# beod.net
KiCad netlist of a schematic drawn in EAGLE
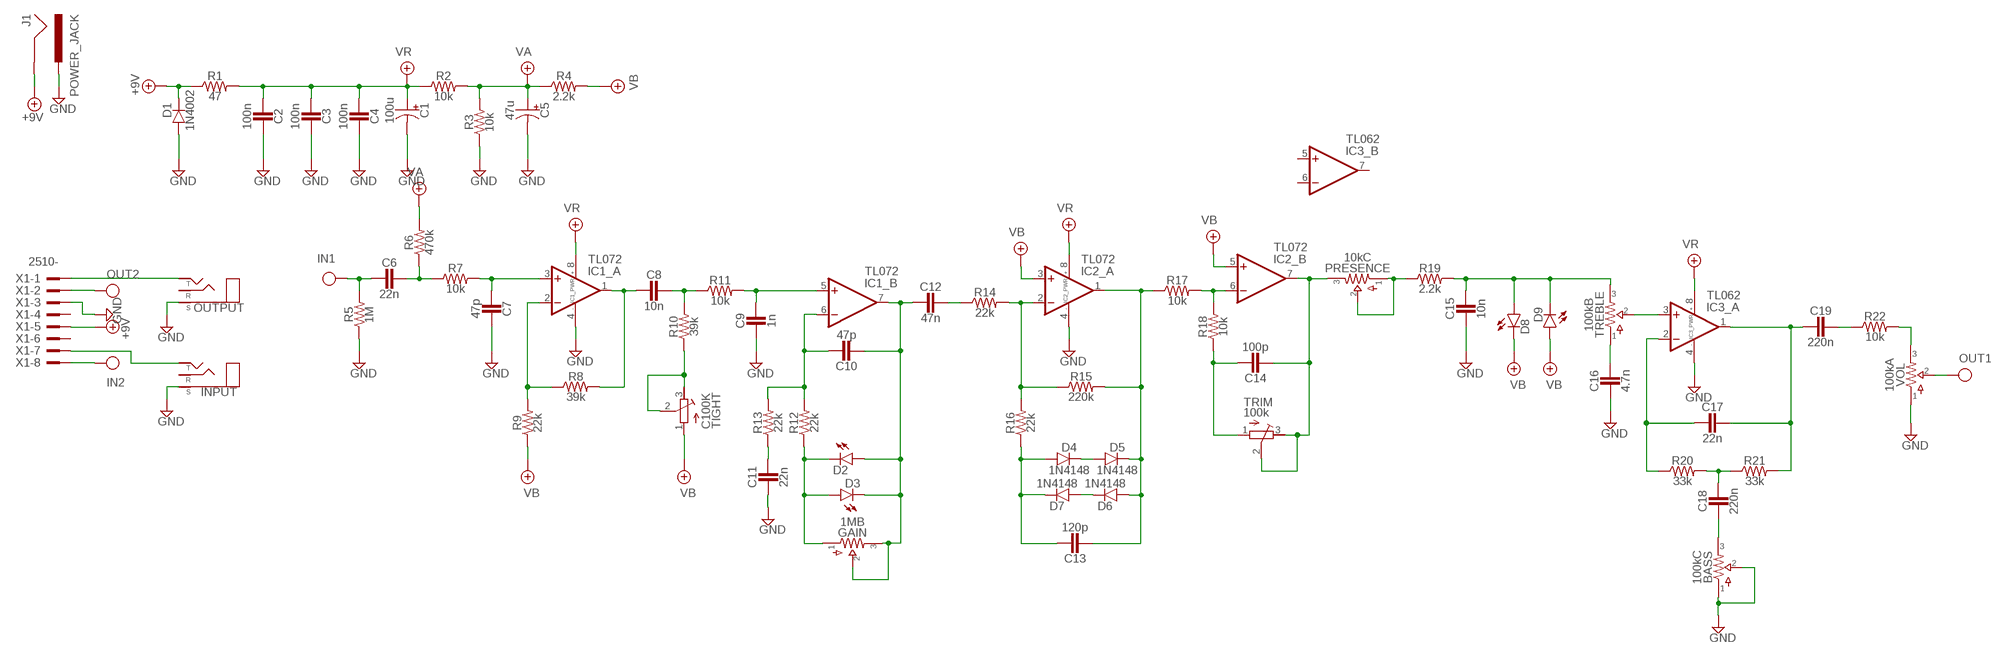
[diagram p0: schematic, sheet 1]

(export (version "E")
  (design (tool "Eeschema 10.0.6"))
  (components
    (comp (ref "BASS")
      (value "100kC")
      (footprint "eagle-import:16MM")
      (libsource (lib "eagle-import") (part "POTS16MM"))
    )
    (comp (ref "C1")
      (value "100u")
      (footprint "eagle-import:040_020")
      (libsource (lib "eagle-import") (part "0400"))
    )
    (comp (ref "C2")
      (value "100n")
      (footprint "eagle-import:050X030_025_2")
      (libsource (lib "eagle-import") (part "CER/FILM2"))
    )
    (comp (ref "C3")
      (value "100n")
      (footprint "eagle-import:050X030_025_2")
      (libsource (lib "eagle-import") (part "CER/FILM2"))
    )
    (comp (ref "C4")
      (value "100n")
      (footprint "eagle-import:050X030_025_2")
      (libsource (lib "eagle-import") (part "CER/FILM2"))
    )
    (comp (ref "C5")
      (value "47u")
      (footprint "eagle-import:040_020")
      (libsource (lib "eagle-import") (part "0400"))
    )
    (comp (ref "C6")
      (value "22n")
      (footprint "eagle-import:BOX_SMALL")
      (libsource (lib "eagle-import") (part "CER/FILMBOX.1"))
    )
    (comp (ref "C7")
      (value "47p")
      (footprint "eagle-import:050X030_025_2")
      (libsource (lib "eagle-import") (part "CER/FILM2"))
    )
    (comp (ref "C8")
      (value "10n")
      (footprint "eagle-import:BOX_SMALL")
      (libsource (lib "eagle-import") (part "CER/FILMBOX.1"))
    )
    (comp (ref "C9")
      (value "1n")
      (footprint "eagle-import:BOX_SMALL")
      (libsource (lib "eagle-import") (part "CER/FILMBOX.1"))
    )
    (comp (ref "C10")
      (value "47p")
      (footprint "eagle-import:050X030_025_2")
      (libsource (lib "eagle-import") (part "CER/FILM2"))
    )
    (comp (ref "C11")
      (value "22n")
      (footprint "eagle-import:BOX_SMALL")
      (libsource (lib "eagle-import") (part "CER/FILMBOX.1"))
    )
    (comp (ref "C12")
      (value "47n")
      (footprint "eagle-import:BOX_SMALL")
      (libsource (lib "eagle-import") (part "CER/FILMBOX.1"))
    )
    (comp (ref "C13")
      (value "120p")
      (footprint "eagle-import:050X030_025_2")
      (libsource (lib "eagle-import") (part "CER/FILM2"))
    )
    (comp (ref "C14")
      (value "100p")
      (footprint "eagle-import:050X030_025_2")
      (libsource (lib "eagle-import") (part "CER/FILM2"))
    )
    (comp (ref "C15")
      (value "10n")
      (footprint "eagle-import:BOX_SMALL")
      (libsource (lib "eagle-import") (part "CER/FILMBOX.1"))
    )
    (comp (ref "C16")
      (value "4.7n")
      (footprint "eagle-import:BOX_SMALL")
      (libsource (lib "eagle-import") (part "CER/FILMBOX.1"))
    )
    (comp (ref "C17")
      (value "22n")
      (footprint "eagle-import:BOX_SMALL")
      (libsource (lib "eagle-import") (part "CER/FILMBOX.1"))
    )
    (comp (ref "C18")
      (value "220n")
      (footprint "eagle-import:BOX_SMALL")
      (libsource (lib "eagle-import") (part "CER/FILMBOX.1"))
    )
    (comp (ref "C19")
      (value "220n")
      (footprint "eagle-import:BOX_SMALL")
      (libsource (lib "eagle-import") (part "CER/FILMBOX.1"))
    )
    (comp (ref "D1")
      (value "1N4002")
      (footprint "eagle-import:DO41-2")
      (libsource (lib "eagle-import") (part "DO41.2"))
    )
    (comp (ref "D2")
      (value "3mm_RED")
      (footprint "eagle-import:3MM_D")
      (libsource (lib "eagle-import") (part "LED"))
    )
    (comp (ref "D3")
      (value "3mm_RED")
      (footprint "eagle-import:3MM_D")
      (libsource (lib "eagle-import") (part "LED"))
    )
    (comp (ref "D4")
      (value "1N4148")
      (footprint "eagle-import:DO35-2")
      (libsource (lib "eagle-import") (part "DO35.2"))
    )
    (comp (ref "D5")
      (value "1N4148")
      (footprint "eagle-import:DO35-2")
      (libsource (lib "eagle-import") (part "DO35.2"))
    )
    (comp (ref "D6")
      (value "1N4148")
      (footprint "eagle-import:DO35-2")
      (libsource (lib "eagle-import") (part "DO35.2"))
    )
    (comp (ref "D7")
      (value "1N4148")
      (footprint "eagle-import:DO35-2")
      (libsource (lib "eagle-import") (part "DO35.2"))
    )
    (comp (ref "D8")
      (value "3mm_RED")
      (footprint "eagle-import:3MM_D")
      (libsource (lib "eagle-import") (part "LED"))
    )
    (comp (ref "D9")
      (value "3mm_RED")
      (footprint "eagle-import:3MM_D")
      (libsource (lib "eagle-import") (part "LED"))
    )
    (comp (ref "GAIN")
      (value "1MB")
      (footprint "eagle-import:16MM")
      (libsource (lib "eagle-import") (part "POTS16MM"))
    )
    (comp (ref "IC1")
      (value "TL072")
      (footprint "eagle-import:DIL0")
      (libsource (lib "eagle-import") (part "DUALTH"))
    )
    (comp (ref "IC2")
      (value "TL072")
      (footprint "eagle-import:DIL0")
      (libsource (lib "eagle-import") (part "DUALTH"))
    )
    (comp (ref "IC3")
      (value "TL062")
      (footprint "eagle-import:DIL0")
      (libsource (lib "eagle-import") (part "DUALTH"))
    )
    (comp (ref "INPUT")
      (value "STEREONMJ")
      (footprint "eagle-import:NMJ6HCD2")
      (libsource (lib "eagle-import") (part "STEREONMJ"))
    )
    (comp (ref "J1")
      (value "POWER_JACK")
      (footprint "eagle-import:POWER_JACK_PTH")
      (libsource (lib "eagle-import") (part "POWER_JACK"))
    )
    (comp (ref "OUTPUT")
      (value "STEREONMJ")
      (footprint "eagle-import:NMJ6HCD2")
      (libsource (lib "eagle-import") (part "STEREONMJ"))
    )
    (comp (ref "PRESENCE")
      (value "10kC")
      (footprint "eagle-import:16MM")
      (libsource (lib "eagle-import") (part "POTS16MM"))
    )
    (comp (ref "R1")
      (value "47")
      (footprint "eagle-import:R0207_3")
      (libsource (lib "eagle-import") (part "R_.3B"))
    )
    (comp (ref "R2")
      (value "10k")
      (footprint "eagle-import:R0207_3")
      (libsource (lib "eagle-import") (part "R_.3B"))
    )
    (comp (ref "R3")
      (value "10k")
      (footprint "eagle-import:R0207_3")
      (libsource (lib "eagle-import") (part "R_.3B"))
    )
    (comp (ref "R4")
      (value "2.2k")
      (footprint "eagle-import:R0207_3")
      (libsource (lib "eagle-import") (part "R_.3B"))
    )
    (comp (ref "R5")
      (value "1M")
      (footprint "eagle-import:R0207_3")
      (libsource (lib "eagle-import") (part "R_.3B"))
    )
    (comp (ref "R6")
      (value "470k")
      (footprint "eagle-import:R0207_3")
      (libsource (lib "eagle-import") (part "R_.3B"))
    )
    (comp (ref "R7")
      (value "10k")
      (footprint "eagle-import:R0207_3")
      (libsource (lib "eagle-import") (part "R_.3B"))
    )
    (comp (ref "R8")
      (value "39k")
      (footprint "eagle-import:R0207_3")
      (libsource (lib "eagle-import") (part "R_.3B"))
    )
    (comp (ref "R9")
      (value "22k")
      (footprint "eagle-import:R0207_3")
      (libsource (lib "eagle-import") (part "R_.3B"))
    )
    (comp (ref "R10")
      (value "39k")
      (footprint "eagle-import:R0207_3")
      (libsource (lib "eagle-import") (part "R_.3B"))
    )
    (comp (ref "R11")
      (value "10k")
      (footprint "eagle-import:R0207_3")
      (libsource (lib "eagle-import") (part "R_.3B"))
    )
    (comp (ref "R12")
      (value "22k")
      (footprint "eagle-import:R0207_3")
      (libsource (lib "eagle-import") (part "R_.3B"))
    )
    (comp (ref "R13")
      (value "22k")
      (footprint "eagle-import:R0207_3")
      (libsource (lib "eagle-import") (part "R_.3B"))
    )
    (comp (ref "R14")
      (value "22k")
      (footprint "eagle-import:R0207_3")
      (libsource (lib "eagle-import") (part "R_.3B"))
    )
    (comp (ref "R15")
      (value "220k")
      (footprint "eagle-import:R0207_3")
      (libsource (lib "eagle-import") (part "R_.3B"))
    )
    (comp (ref "R16")
      (value "22k")
      (footprint "eagle-import:R0207_3")
      (libsource (lib "eagle-import") (part "R_.3B"))
    )
    (comp (ref "R17")
      (value "10k")
      (footprint "eagle-import:R0207_3")
      (libsource (lib "eagle-import") (part "R_.3B"))
    )
    (comp (ref "R18")
      (value "10k")
      (footprint "eagle-import:R0207_3")
      (libsource (lib "eagle-import") (part "R_.3B"))
    )
    (comp (ref "R19")
      (value "2.2k")
      (footprint "eagle-import:R0207_3")
      (libsource (lib "eagle-import") (part "R_.3B"))
    )
    (comp (ref "R20")
      (value "33k")
      (footprint "eagle-import:R0207_3")
      (libsource (lib "eagle-import") (part "R_.3B"))
    )
    (comp (ref "R21")
      (value "33k")
      (footprint "eagle-import:R0207_3")
      (libsource (lib "eagle-import") (part "R_.3B"))
    )
    (comp (ref "R22")
      (value "10k")
      (footprint "eagle-import:R0207_3")
      (libsource (lib "eagle-import") (part "R_.3B"))
    )
    (comp (ref "TIGHT")
      (value "C100K")
      (footprint "eagle-import:RTRIM3296W")
      (libsource (lib "eagle-import") (part "R-TRIMM3296W"))
    )
    (comp (ref "TREBLE")
      (value "100kB")
      (footprint "eagle-import:16MM")
      (libsource (lib "eagle-import") (part "POTS16MM"))
    )
    (comp (ref "TRIM")
      (value "100k")
      (footprint "eagle-import:RTRIM3296W")
      (libsource (lib "eagle-import") (part "R-TRIMM3296W"))
    )
    (comp (ref "VOL")
      (value "100kA")
      (footprint "eagle-import:16MM")
      (libsource (lib "eagle-import") (part "POTS16MM"))
    )
    (comp (ref "X1")
      (value "2510-")
      (footprint "eagle-import:PAK100_2500-10")
      (fields (field (name "MF") "3M") (field (name "MPN") "2510-6002UB"))
      (libsource (lib "eagle-import") (part "2510-"))
    )
  )
  (nets
    (net (code "1") (name "+9V") (class "Default")
      (node (ref "D1") (pin "C") (pinfunction "C_C") (pintype "passive"))
      (node (ref "J1") (pin "GND") (pinfunction "GND_GND") (pintype "bidirectional"))
      (node (ref "R1") (pin "1") (pinfunction "1_1") (pintype "passive"))
      (node (ref "X1") (pin "5") (pinfunction "KL_5") (pintype "passive"))
    )
    (net (code "2") (name "GND") (class "Default")
      (node (ref "BASS") (pin "1") (pinfunction "1_1") (pintype "passive"))
      (node (ref "BASS") (pin "2") (pinfunction "2_2") (pintype "passive"))
      (node (ref "C1") (pin "-") (pinfunction "-_-") (pintype "passive"))
      (node (ref "C11") (pin "2") (pinfunction "2_2") (pintype "passive"))
      (node (ref "C15") (pin "2") (pinfunction "2_2") (pintype "passive"))
      (node (ref "C16") (pin "2") (pinfunction "2_2") (pintype "passive"))
      (node (ref "C2") (pin "1") (pinfunction "1_1") (pintype "passive"))
      (node (ref "C3") (pin "1") (pinfunction "1_1") (pintype "passive"))
      (node (ref "C4") (pin "1") (pinfunction "1_1") (pintype "passive"))
      (node (ref "C5") (pin "-") (pinfunction "-_-") (pintype "passive"))
      (node (ref "C7") (pin "1") (pinfunction "1_1") (pintype "passive"))
      (node (ref "C9") (pin "2") (pinfunction "2_2") (pintype "passive"))
      (node (ref "D1") (pin "A") (pinfunction "A_A") (pintype "passive"))
      (node (ref "IC1") (pin "4") (pinfunction "V-_4") (pintype "power_in"))
      (node (ref "IC2") (pin "4") (pinfunction "V-_4") (pintype "power_in"))
      (node (ref "IC3") (pin "4") (pinfunction "V-_4") (pintype "power_in"))
      (node (ref "INPUT") (pin "S") (pinfunction "S_S") (pintype "passive"))
      (node (ref "J1") (pin "PWR") (pinfunction "PWR_PWR") (pintype "bidirectional"))
      (node (ref "OUTPUT") (pin "S") (pinfunction "S_S") (pintype "passive"))
      (node (ref "R3") (pin "1") (pinfunction "1_1") (pintype "passive"))
      (node (ref "R5") (pin "1") (pinfunction "1_1") (pintype "passive"))
      (node (ref "VOL") (pin "1") (pinfunction "1_1") (pintype "passive"))
      (node (ref "X1") (pin "3") (pinfunction "KL_3") (pintype "passive"))
    )
    (net (code "3") (name "IN") (class "Default")
      (node (ref "C6") (pin "2") (pinfunction "2_2") (pintype "passive"))
      (node (ref "R5") (pin "2") (pinfunction "2_2") (pintype "passive"))
      (node (ref "X1") (pin "8") (pinfunction "KL_8") (pintype "passive"))
    )
    (net (code "4") (name "Net-(BASS-Pad3)") (class "Default")
      (node (ref "BASS") (pin "3") (pinfunction "3_3") (pintype "passive"))
      (node (ref "C18") (pin "2") (pinfunction "2_2") (pintype "passive"))
    )
    (net (code "5") (name "Net-(C6-Pad1)") (class "Default")
      (node (ref "C6") (pin "1") (pinfunction "1_1") (pintype "passive"))
      (node (ref "R6") (pin "1") (pinfunction "1_1") (pintype "passive"))
      (node (ref "R7") (pin "1") (pinfunction "1_1") (pintype "passive"))
    )
    (net (code "6") (name "Net-(C8-Pad1)") (class "Default")
      (node (ref "C8") (pin "1") (pinfunction "1_1") (pintype "passive"))
      (node (ref "R10") (pin "2") (pinfunction "2_2") (pintype "passive"))
      (node (ref "R11") (pin "1") (pinfunction "1_1") (pintype "passive"))
    )
    (net (code "7") (name "Net-(C11-Pad1)") (class "Default")
      (node (ref "C11") (pin "1") (pinfunction "1_1") (pintype "passive"))
      (node (ref "R13") (pin "1") (pinfunction "1_1") (pintype "passive"))
    )
    (net (code "8") (name "Net-(C12-Pad1)") (class "Default")
      (node (ref "C12") (pin "1") (pinfunction "1_1") (pintype "passive"))
      (node (ref "R14") (pin "1") (pinfunction "1_1") (pintype "passive"))
    )
    (net (code "9") (name "Net-(C13-Pad1)") (class "Default")
      (node (ref "C13") (pin "1") (pinfunction "1_1") (pintype "passive"))
      (node (ref "D4") (pin "A") (pinfunction "A_A") (pintype "passive"))
      (node (ref "D7") (pin "C") (pinfunction "C_C") (pintype "passive"))
      (node (ref "R16") (pin "1") (pinfunction "1_1") (pintype "passive"))
    )
    (net (code "10") (name "Net-(C16-Pad1)") (class "Default")
      (node (ref "C16") (pin "1") (pinfunction "1_1") (pintype "passive"))
      (node (ref "TREBLE") (pin "1") (pinfunction "1_1") (pintype "passive"))
    )
    (net (code "11") (name "Net-(C18-Pad1)") (class "Default")
      (node (ref "C18") (pin "1") (pinfunction "1_1") (pintype "passive"))
      (node (ref "R20") (pin "2") (pinfunction "2_2") (pintype "passive"))
      (node (ref "R21") (pin "1") (pinfunction "1_1") (pintype "passive"))
    )
    (net (code "12") (name "Net-(C19-Pad1)") (class "Default")
      (node (ref "C19") (pin "1") (pinfunction "1_1") (pintype "passive"))
      (node (ref "R22") (pin "1") (pinfunction "1_1") (pintype "passive"))
    )
    (net (code "13") (name "Net-(D2-A)") (class "Default")
      (node (ref "C10") (pin "2") (pinfunction "2_2") (pintype "passive"))
      (node (ref "C12") (pin "2") (pinfunction "2_2") (pintype "passive"))
      (node (ref "D2") (pin "ANODE") (pinfunction "A_ANODE") (pintype "passive"))
      (node (ref "D3") (pin "P$1") (pinfunction "C_P$1") (pintype "passive"))
      (node (ref "GAIN") (pin "2") (pinfunction "2_2") (pintype "passive"))
      (node (ref "GAIN") (pin "3") (pinfunction "3_3") (pintype "passive"))
      (node (ref "IC1") (pin "7") (pinfunction "OUT_7") (pintype "output"))
    )
    (net (code "14") (name "Net-(D2-C)") (class "Default")
      (node (ref "D2") (pin "P$1") (pinfunction "C_P$1") (pintype "passive"))
      (node (ref "D3") (pin "ANODE") (pinfunction "A_ANODE") (pintype "passive"))
      (node (ref "GAIN") (pin "1") (pinfunction "1_1") (pintype "passive"))
      (node (ref "R12") (pin "1") (pinfunction "1_1") (pintype "passive"))
    )
    (net (code "15") (name "Net-(D4-PadC)") (class "Default")
      (node (ref "D4") (pin "C") (pinfunction "C_C") (pintype "passive"))
      (node (ref "D5") (pin "A") (pinfunction "A_A") (pintype "passive"))
    )
    (net (code "16") (name "Net-(D6-PadC)") (class "Default")
      (node (ref "D6") (pin "C") (pinfunction "C_C") (pintype "passive"))
      (node (ref "D7") (pin "A") (pinfunction "A_A") (pintype "passive"))
    )
    (net (code "17") (name "Net-(D8-A)") (class "Default")
      (node (ref "C15") (pin "1") (pinfunction "1_1") (pintype "passive"))
      (node (ref "D8") (pin "ANODE") (pinfunction "A_ANODE") (pintype "passive"))
      (node (ref "D9") (pin "P$1") (pinfunction "C_P$1") (pintype "passive"))
      (node (ref "R19") (pin "2") (pinfunction "2_2") (pintype "passive"))
      (node (ref "TREBLE") (pin "3") (pinfunction "3_3") (pintype "passive"))
    )
    (net (code "18") (name "Net-(IC1A-+IN)") (class "Default")
      (node (ref "C7") (pin "2") (pinfunction "2_2") (pintype "passive"))
      (node (ref "IC1") (pin "3") (pinfunction "+IN_3") (pintype "input"))
      (node (ref "R7") (pin "2") (pinfunction "2_2") (pintype "passive"))
    )
    (net (code "19") (name "Net-(IC1A--IN)") (class "Default")
      (node (ref "IC1") (pin "2") (pinfunction "-IN_2") (pintype "input"))
      (node (ref "R8") (pin "1") (pinfunction "1_1") (pintype "passive"))
      (node (ref "R9") (pin "2") (pinfunction "2_2") (pintype "passive"))
    )
    (net (code "20") (name "Net-(IC1A-OUT)") (class "Default")
      (node (ref "C8") (pin "2") (pinfunction "2_2") (pintype "passive"))
      (node (ref "IC1") (pin "1") (pinfunction "OUT_1") (pintype "output"))
      (node (ref "R8") (pin "2") (pinfunction "2_2") (pintype "passive"))
    )
    (net (code "21") (name "Net-(IC1B-+IN)") (class "Default")
      (node (ref "C9") (pin "1") (pinfunction "1_1") (pintype "passive"))
      (node (ref "IC1") (pin "5") (pinfunction "+IN_5") (pintype "input"))
      (node (ref "R11") (pin "2") (pinfunction "2_2") (pintype "passive"))
    )
    (net (code "22") (name "Net-(IC1B--IN)") (class "Default")
      (node (ref "C10") (pin "1") (pinfunction "1_1") (pintype "passive"))
      (node (ref "IC1") (pin "6") (pinfunction "-IN_6") (pintype "input"))
      (node (ref "R12") (pin "2") (pinfunction "2_2") (pintype "passive"))
      (node (ref "R13") (pin "2") (pinfunction "2_2") (pintype "passive"))
    )
    (net (code "23") (name "Net-(IC2A--IN)") (class "Default")
      (node (ref "IC2") (pin "2") (pinfunction "-IN_2") (pintype "input"))
      (node (ref "R14") (pin "2") (pinfunction "2_2") (pintype "passive"))
      (node (ref "R15") (pin "1") (pinfunction "1_1") (pintype "passive"))
      (node (ref "R16") (pin "2") (pinfunction "2_2") (pintype "passive"))
    )
    (net (code "24") (name "Net-(IC2A-OUT)") (class "Default")
      (node (ref "C13") (pin "2") (pinfunction "2_2") (pintype "passive"))
      (node (ref "D5") (pin "C") (pinfunction "C_C") (pintype "passive"))
      (node (ref "D6") (pin "A") (pinfunction "A_A") (pintype "passive"))
      (node (ref "IC2") (pin "1") (pinfunction "OUT_1") (pintype "output"))
      (node (ref "R15") (pin "2") (pinfunction "2_2") (pintype "passive"))
      (node (ref "R17") (pin "1") (pinfunction "1_1") (pintype "passive"))
    )
    (net (code "25") (name "Net-(IC2B--IN)") (class "Default")
      (node (ref "IC2") (pin "6") (pinfunction "-IN_6") (pintype "input"))
      (node (ref "R17") (pin "2") (pinfunction "2_2") (pintype "passive"))
      (node (ref "R18") (pin "2") (pinfunction "2_2") (pintype "passive"))
    )
    (net (code "26") (name "Net-(IC2B-OUT)") (class "Default")
      (node (ref "C14") (pin "2") (pinfunction "2_2") (pintype "passive"))
      (node (ref "IC2") (pin "7") (pinfunction "OUT_7") (pintype "output"))
      (node (ref "PRESENCE") (pin "3") (pinfunction "3_3") (pintype "passive"))
      (node (ref "TRIM") (pin "2") (pinfunction "S_2") (pintype "passive"))
      (node (ref "TRIM") (pin "3") (pinfunction "E_3") (pintype "passive"))
    )
    (net (code "27") (name "Net-(IC3A-+IN)") (class "Default")
      (node (ref "IC3") (pin "3") (pinfunction "+IN_3") (pintype "input"))
      (node (ref "TREBLE") (pin "2") (pinfunction "2_2") (pintype "passive"))
    )
    (net (code "28") (name "Net-(IC3A--IN)") (class "Default")
      (node (ref "C17") (pin "2") (pinfunction "2_2") (pintype "passive"))
      (node (ref "IC3") (pin "2") (pinfunction "-IN_2") (pintype "input"))
      (node (ref "R20") (pin "1") (pinfunction "1_1") (pintype "passive"))
    )
    (net (code "29") (name "Net-(IC3A-OUT)") (class "Default")
      (node (ref "C17") (pin "1") (pinfunction "1_1") (pintype "passive"))
      (node (ref "C19") (pin "2") (pinfunction "2_2") (pintype "passive"))
      (node (ref "IC3") (pin "1") (pinfunction "OUT_1") (pintype "output"))
      (node (ref "R21") (pin "2") (pinfunction "2_2") (pintype "passive"))
    )
    (net (code "30") (name "Net-(PRESENCE-Pad1)") (class "Default")
      (node (ref "PRESENCE") (pin "1") (pinfunction "1_1") (pintype "passive"))
      (node (ref "PRESENCE") (pin "2") (pinfunction "2_2") (pintype "passive"))
      (node (ref "R19") (pin "1") (pinfunction "1_1") (pintype "passive"))
    )
    (net (code "31") (name "Net-(R22-Pad2)") (class "Default")
      (node (ref "R22") (pin "2") (pinfunction "2_2") (pintype "passive"))
      (node (ref "VOL") (pin "3") (pinfunction "3_3") (pintype "passive"))
    )
    (net (code "32") (name "Net-(TIGHT-E)") (class "Default")
      (node (ref "R10") (pin "1") (pinfunction "1_1") (pintype "passive"))
      (node (ref "TIGHT") (pin "2") (pinfunction "S_2") (pintype "passive"))
      (node (ref "TIGHT") (pin "3") (pinfunction "E_3") (pintype "passive"))
    )
    (net (code "33") (name "Net-(TRIM-A)") (class "Default")
      (node (ref "C14") (pin "1") (pinfunction "1_1") (pintype "passive"))
      (node (ref "R18") (pin "1") (pinfunction "1_1") (pintype "passive"))
      (node (ref "TRIM") (pin "1") (pinfunction "A_1") (pintype "passive"))
    )
    (net (code "34") (name "Net-(X1A-KL)") (class "Default")
      (node (ref "OUTPUT") (pin "T") (pinfunction "T_T") (pintype "passive"))
      (node (ref "X1") (pin "1") (pinfunction "KL_1") (pintype "passive"))
    )
    (net (code "35") (name "Net-(X1G-KL)") (class "Default")
      (node (ref "INPUT") (pin "T") (pinfunction "T_T") (pintype "passive"))
      (node (ref "X1") (pin "7") (pinfunction "KL_7") (pintype "passive"))
    )
    (net (code "36") (name "OUT") (class "Default")
      (node (ref "VOL") (pin "2") (pinfunction "2_2") (pintype "passive"))
      (node (ref "X1") (pin "2") (pinfunction "KL_2") (pintype "passive"))
    )
    (net (code "37") (name "VA") (class "Default")
      (node (ref "C5") (pin "+") (pinfunction "+_+") (pintype "passive"))
      (node (ref "R2") (pin "2") (pinfunction "2_2") (pintype "passive"))
      (node (ref "R3") (pin "2") (pinfunction "2_2") (pintype "passive"))
      (node (ref "R4") (pin "1") (pinfunction "1_1") (pintype "passive"))
      (node (ref "R6") (pin "2") (pinfunction "2_2") (pintype "passive"))
    )
    (net (code "38") (name "VB") (class "Default")
      (node (ref "D8") (pin "P$1") (pinfunction "C_P$1") (pintype "passive"))
      (node (ref "D9") (pin "ANODE") (pinfunction "A_ANODE") (pintype "passive"))
      (node (ref "IC2") (pin "3") (pinfunction "+IN_3") (pintype "input"))
      (node (ref "IC2") (pin "5") (pinfunction "+IN_5") (pintype "input"))
      (node (ref "R4") (pin "2") (pinfunction "2_2") (pintype "passive"))
      (node (ref "R9") (pin "1") (pinfunction "1_1") (pintype "passive"))
      (node (ref "TIGHT") (pin "1") (pinfunction "A_1") (pintype "passive"))
    )
    (net (code "39") (name "VR") (class "Default")
      (node (ref "C1") (pin "+") (pinfunction "+_+") (pintype "passive"))
      (node (ref "C2") (pin "2") (pinfunction "2_2") (pintype "passive"))
      (node (ref "C3") (pin "2") (pinfunction "2_2") (pintype "passive"))
      (node (ref "C4") (pin "2") (pinfunction "2_2") (pintype "passive"))
      (node (ref "IC1") (pin "8") (pinfunction "V+_8") (pintype "power_in"))
      (node (ref "IC2") (pin "8") (pinfunction "V+_8") (pintype "power_in"))
      (node (ref "IC3") (pin "8") (pinfunction "V+_8") (pintype "power_in"))
      (node (ref "R1") (pin "2") (pinfunction "2_2") (pintype "passive"))
      (node (ref "R2") (pin "1") (pinfunction "1_1") (pintype "passive"))
    )
    (net (code "40") (name "unconnected-(IC3B-+IN-Pad5)") (class "Default")
      (node (ref "IC3") (pin "5") (pinfunction "+IN_5") (pintype "input"))
    )
    (net (code "41") (name "unconnected-(IC3B--IN-Pad6)") (class "Default")
      (node (ref "IC3") (pin "6") (pinfunction "-IN_6") (pintype "input"))
    )
    (net (code "42") (name "unconnected-(IC3B-OUT-Pad7)") (class "Default")
      (node (ref "IC3") (pin "7") (pinfunction "OUT_7") (pintype "output"))
    )
    (net (code "43") (name "unconnected-(INPUT-PadR)") (class "Default")
      (node (ref "INPUT") (pin "R") (pinfunction "R_R") (pintype "passive"))
    )
    (net (code "44") (name "unconnected-(OUTPUT-PadR)") (class "Default")
      (node (ref "OUTPUT") (pin "R") (pinfunction "R_R") (pintype "passive"))
    )
    (net (code "45") (name "unconnected-(X1D-KL-Pad4)") (class "Default")
      (node (ref "X1") (pin "4") (pinfunction "KL_4") (pintype "passive"))
    )
    (net (code "46") (name "unconnected-(X1F-KL-Pad6)") (class "Default")
      (node (ref "X1") (pin "6") (pinfunction "KL_6") (pintype "passive"))
    )
  )
)
